# CW340_USERIO_Header.net
KiCad netlist of a schematic drawn in Altium Designer
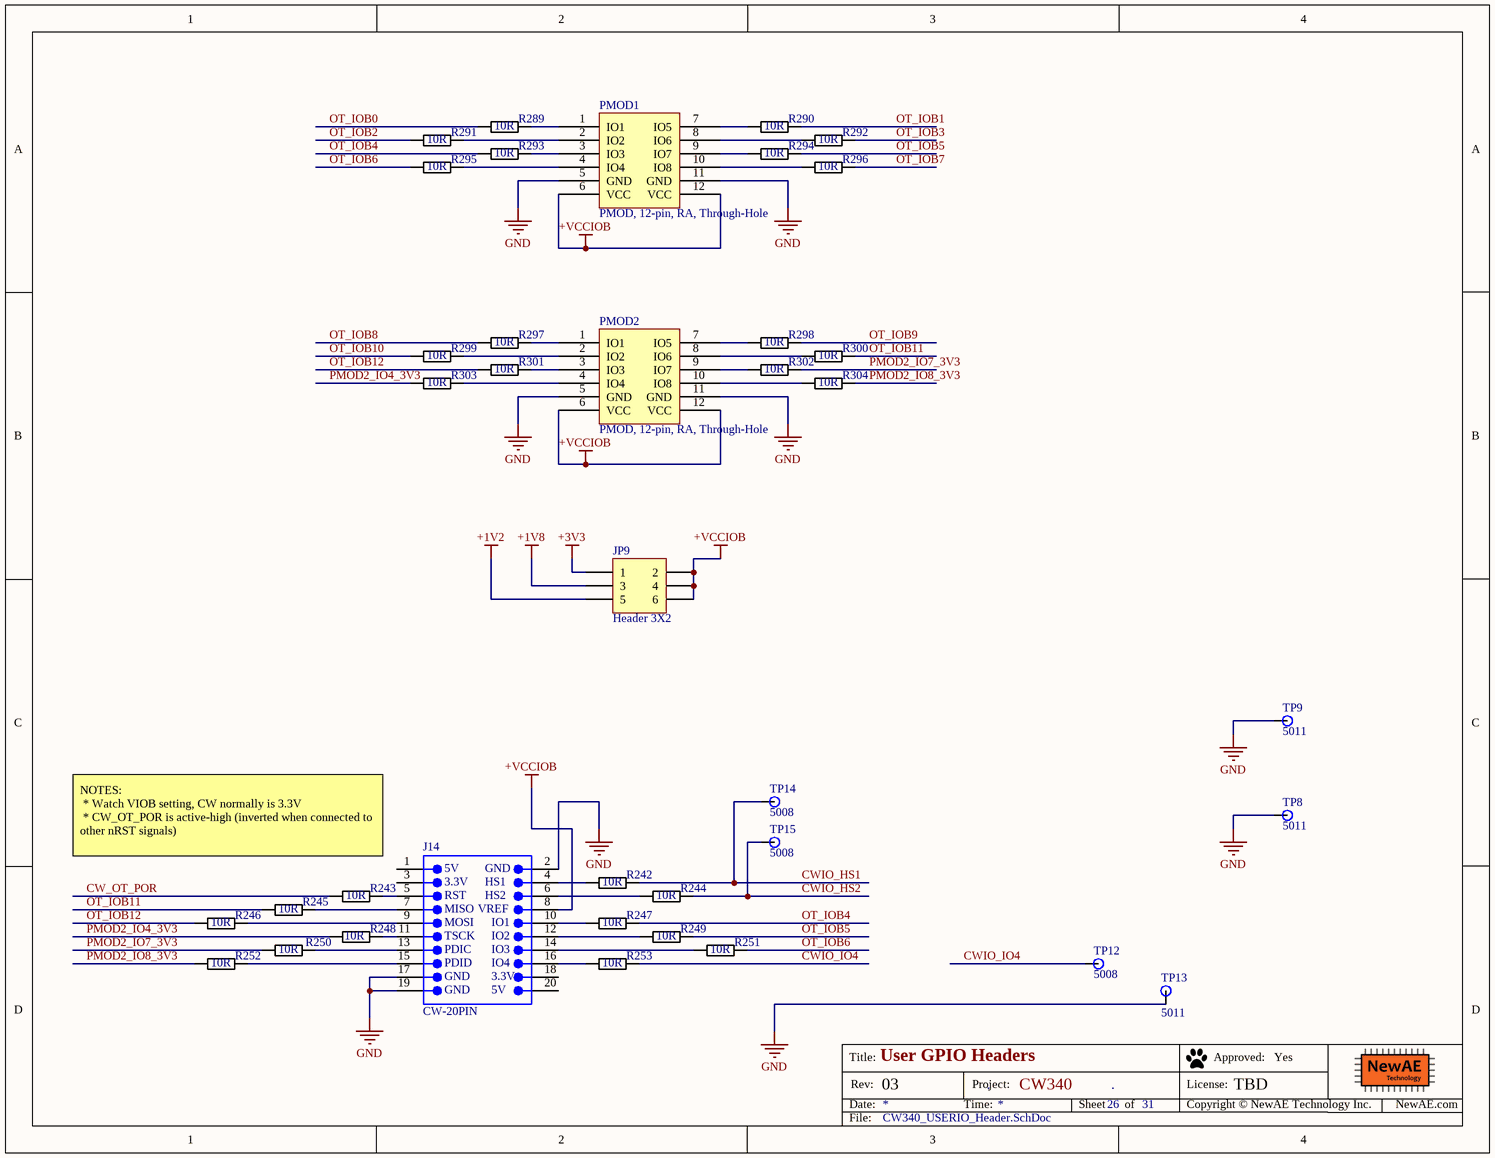
[diagram p0: CW340_USERIO_Header.SchDoc]

(export (version "E")
  (design (tool "Eeschema 10.0.6"))
  (components
    (comp (ref "J14")
      (value "CW-20PIN")
      (footprint "CONN_10x2_SHROUDED_2.54mm")
      (fields (field (name "PART NUMBER") "CW20PIN_TH"))
      (libsource (lib "NewAE_AltiumLib") (part "CW20PIN_TH_RA"))
    )
    (comp (ref "JP9")
      (value "Header 3X2")
      (footprint "HDR2X3")
      (description "Header, 3-Pin, Dual row")
      (fields (field (name "PUBLISHER") "Altium Limited"))
      (libsource (lib "Miscellaneous Connectors") (part "Header 3X2"))
    )
    (comp (ref "PMOD1")
      (value "PMOD, 12-pin, RA, Through-Hole")
      (footprint "SAMTEC_SSW_106_02_X_D_RA_PMOD")
      (fields (field (name "PART NUMBER") "PMOD_2ROW_FEMALERATH"))
      (libsource (lib "NewAE_AltiumLib") (part "12PIN_RA_FEMALE"))
    )
    (comp (ref "PMOD2")
      (value "PMOD, 12-pin, RA, Through-Hole")
      (footprint "SAMTEC_SSW_106_02_X_D_RA_PMOD")
      (fields (field (name "PART NUMBER") "PMOD_2ROW_FEMALERATH"))
      (libsource (lib "NewAE_AltiumLib") (part "12PIN_RA_FEMALE"))
    )
    (comp (ref "R242")
      (value "10R")
      (footprint "RESC1005X40N")
      (description "10R res, 0402, 1%, 1/16W")
      (fields (field (name "PART NUMBER") "RCHIP-10R-0402") (field (name "TOLERANCE") "1%"))
      (libsource (lib "NewAE_AltiumLib") (part "RES-EU"))
    )
    (comp (ref "R243")
      (value "10R")
      (footprint "RESC1005X40N")
      (description "10R res, 0402, 1%, 1/16W")
      (fields (field (name "PART NUMBER") "RCHIP-10R-0402") (field (name "TOLERANCE") "1%"))
      (libsource (lib "NewAE_AltiumLib") (part "RES-EU"))
    )
    (comp (ref "R244")
      (value "10R")
      (footprint "RESC1005X40N")
      (description "10R res, 0402, 1%, 1/16W")
      (fields (field (name "PART NUMBER") "RCHIP-10R-0402") (field (name "TOLERANCE") "1%"))
      (libsource (lib "NewAE_AltiumLib") (part "RES-EU"))
    )
    (comp (ref "R245")
      (value "10R")
      (footprint "RESC1005X40N")
      (description "10R res, 0402, 1%, 1/16W")
      (fields (field (name "PART NUMBER") "RCHIP-10R-0402") (field (name "TOLERANCE") "1%"))
      (libsource (lib "NewAE_AltiumLib") (part "RES-EU"))
    )
    (comp (ref "R246")
      (value "10R")
      (footprint "RESC1005X40N")
      (description "10R res, 0402, 1%, 1/16W")
      (fields (field (name "PART NUMBER") "RCHIP-10R-0402") (field (name "TOLERANCE") "1%"))
      (libsource (lib "NewAE_AltiumLib") (part "RES-EU"))
    )
    (comp (ref "R247")
      (value "10R")
      (footprint "RESC1005X40N")
      (description "10R res, 0402, 1%, 1/16W")
      (fields (field (name "PART NUMBER") "RCHIP-10R-0402") (field (name "TOLERANCE") "1%"))
      (libsource (lib "NewAE_AltiumLib") (part "RES-EU"))
    )
    (comp (ref "R248")
      (value "10R")
      (footprint "RESC1005X40N")
      (description "10R res, 0402, 1%, 1/16W")
      (fields (field (name "PART NUMBER") "RCHIP-10R-0402") (field (name "TOLERANCE") "1%"))
      (libsource (lib "NewAE_AltiumLib") (part "RES-EU"))
    )
    (comp (ref "R249")
      (value "10R")
      (footprint "RESC1005X40N")
      (description "10R res, 0402, 1%, 1/16W")
      (fields (field (name "PART NUMBER") "RCHIP-10R-0402") (field (name "TOLERANCE") "1%"))
      (libsource (lib "NewAE_AltiumLib") (part "RES-EU"))
    )
    (comp (ref "R250")
      (value "10R")
      (footprint "RESC1005X40N")
      (description "10R res, 0402, 1%, 1/16W")
      (fields (field (name "PART NUMBER") "RCHIP-10R-0402") (field (name "TOLERANCE") "1%"))
      (libsource (lib "NewAE_AltiumLib") (part "RES-EU"))
    )
    (comp (ref "R251")
      (value "10R")
      (footprint "RESC1005X40N")
      (description "10R res, 0402, 1%, 1/16W")
      (fields (field (name "PART NUMBER") "RCHIP-10R-0402") (field (name "TOLERANCE") "1%"))
      (libsource (lib "NewAE_AltiumLib") (part "RES-EU"))
    )
    (comp (ref "R252")
      (value "10R")
      (footprint "RESC1005X40N")
      (description "10R res, 0402, 1%, 1/16W")
      (fields (field (name "PART NUMBER") "RCHIP-10R-0402") (field (name "TOLERANCE") "1%"))
      (libsource (lib "NewAE_AltiumLib") (part "RES-EU"))
    )
    (comp (ref "R253")
      (value "10R")
      (footprint "RESC1005X40N")
      (description "10R res, 0402, 1%, 1/16W")
      (fields (field (name "PART NUMBER") "RCHIP-10R-0402") (field (name "TOLERANCE") "1%"))
      (libsource (lib "NewAE_AltiumLib") (part "RES-EU"))
    )
    (comp (ref "R289")
      (value "10R")
      (footprint "RESC1005X40N")
      (description "10R res, 0402, 1%, 1/16W")
      (fields (field (name "PART NUMBER") "RCHIP-10R-0402") (field (name "TOLERANCE") "1%"))
      (libsource (lib "NewAE_AltiumLib") (part "RES-EU"))
    )
    (comp (ref "R290")
      (value "10R")
      (footprint "RESC1005X40N")
      (description "10R res, 0402, 1%, 1/16W")
      (fields (field (name "PART NUMBER") "RCHIP-10R-0402") (field (name "TOLERANCE") "1%"))
      (libsource (lib "NewAE_AltiumLib") (part "RES-EU"))
    )
    (comp (ref "R291")
      (value "10R")
      (footprint "RESC1005X40N")
      (description "10R res, 0402, 1%, 1/16W")
      (fields (field (name "PART NUMBER") "RCHIP-10R-0402") (field (name "TOLERANCE") "1%"))
      (libsource (lib "NewAE_AltiumLib") (part "RES-EU"))
    )
    (comp (ref "R292")
      (value "10R")
      (footprint "RESC1005X40N")
      (description "10R res, 0402, 1%, 1/16W")
      (fields (field (name "PART NUMBER") "RCHIP-10R-0402") (field (name "TOLERANCE") "1%"))
      (libsource (lib "NewAE_AltiumLib") (part "RES-EU"))
    )
    (comp (ref "R293")
      (value "10R")
      (footprint "RESC1005X40N")
      (description "10R res, 0402, 1%, 1/16W")
      (fields (field (name "PART NUMBER") "RCHIP-10R-0402") (field (name "TOLERANCE") "1%"))
      (libsource (lib "NewAE_AltiumLib") (part "RES-EU"))
    )
    (comp (ref "R294")
      (value "10R")
      (footprint "RESC1005X40N")
      (description "10R res, 0402, 1%, 1/16W")
      (fields (field (name "PART NUMBER") "RCHIP-10R-0402") (field (name "TOLERANCE") "1%"))
      (libsource (lib "NewAE_AltiumLib") (part "RES-EU"))
    )
    (comp (ref "R295")
      (value "10R")
      (footprint "RESC1005X40N")
      (description "10R res, 0402, 1%, 1/16W")
      (fields (field (name "PART NUMBER") "RCHIP-10R-0402") (field (name "TOLERANCE") "1%"))
      (libsource (lib "NewAE_AltiumLib") (part "RES-EU"))
    )
    (comp (ref "R296")
      (value "10R")
      (footprint "RESC1005X40N")
      (description "10R res, 0402, 1%, 1/16W")
      (fields (field (name "PART NUMBER") "RCHIP-10R-0402") (field (name "TOLERANCE") "1%"))
      (libsource (lib "NewAE_AltiumLib") (part "RES-EU"))
    )
    (comp (ref "R297")
      (value "10R")
      (footprint "RESC1005X40N")
      (description "10R res, 0402, 1%, 1/16W")
      (fields (field (name "PART NUMBER") "RCHIP-10R-0402") (field (name "TOLERANCE") "1%"))
      (libsource (lib "NewAE_AltiumLib") (part "RES-EU"))
    )
    (comp (ref "R298")
      (value "10R")
      (footprint "RESC1005X40N")
      (description "10R res, 0402, 1%, 1/16W")
      (fields (field (name "PART NUMBER") "RCHIP-10R-0402") (field (name "TOLERANCE") "1%"))
      (libsource (lib "NewAE_AltiumLib") (part "RES-EU"))
    )
    (comp (ref "R299")
      (value "10R")
      (footprint "RESC1005X40N")
      (description "10R res, 0402, 1%, 1/16W")
      (fields (field (name "PART NUMBER") "RCHIP-10R-0402") (field (name "TOLERANCE") "1%"))
      (libsource (lib "NewAE_AltiumLib") (part "RES-EU"))
    )
    (comp (ref "R300")
      (value "10R")
      (footprint "RESC1005X40N")
      (description "10R res, 0402, 1%, 1/16W")
      (fields (field (name "PART NUMBER") "RCHIP-10R-0402") (field (name "TOLERANCE") "1%"))
      (libsource (lib "NewAE_AltiumLib") (part "RES-EU"))
    )
    (comp (ref "R301")
      (value "10R")
      (footprint "RESC1005X40N")
      (description "10R res, 0402, 1%, 1/16W")
      (fields (field (name "PART NUMBER") "RCHIP-10R-0402") (field (name "TOLERANCE") "1%"))
      (libsource (lib "NewAE_AltiumLib") (part "RES-EU"))
    )
    (comp (ref "R302")
      (value "10R")
      (footprint "RESC1005X40N")
      (description "10R res, 0402, 1%, 1/16W")
      (fields (field (name "PART NUMBER") "RCHIP-10R-0402") (field (name "TOLERANCE") "1%"))
      (libsource (lib "NewAE_AltiumLib") (part "RES-EU"))
    )
    (comp (ref "R303")
      (value "10R")
      (footprint "RESC1005X40N")
      (description "10R res, 0402, 1%, 1/16W")
      (fields (field (name "PART NUMBER") "RCHIP-10R-0402") (field (name "TOLERANCE") "1%"))
      (libsource (lib "NewAE_AltiumLib") (part "RES-EU"))
    )
    (comp (ref "R304")
      (value "10R")
      (footprint "RESC1005X40N")
      (description "10R res, 0402, 1%, 1/16W")
      (fields (field (name "PART NUMBER") "RCHIP-10R-0402") (field (name "TOLERANCE") "1%"))
      (libsource (lib "NewAE_AltiumLib") (part "RES-EU"))
    )
    (comp (ref "TP8")
      (value "5011")
      (footprint "KEYSTONE5011")
      (description "TEST POINT PC MULTI PURPOSE BLK")
      (fields (field (name "PART NUMBER") "KEYSTONE_5011"))
      (libsource (lib "NewAE_AltiumLib") (part "KEYSTONE_5011"))
    )
    (comp (ref "TP9")
      (value "5011")
      (footprint "KEYSTONE5011")
      (description "TEST POINT PC MULTI PURPOSE BLK")
      (fields (field (name "PART NUMBER") "KEYSTONE_5011"))
      (libsource (lib "NewAE_AltiumLib") (part "KEYSTONE_5011"))
    )
    (comp (ref "TP12")
      (value "5008")
      (footprint "KEYSTONE5008")
      (description "TEST POINT PC COMPACT .063\"D ORG")
      (fields (field (name "PART NUMBER") "KEYSTONE_5008"))
      (libsource (lib "NewAE_AltiumLib") (part "KEYSTONE_5008"))
    )
    (comp (ref "TP13")
      (value "5011")
      (footprint "KEYSTONE5011")
      (description "TEST POINT PC MULTI PURPOSE BLK")
      (fields (field (name "PART NUMBER") "KEYSTONE_5011"))
      (libsource (lib "NewAE_AltiumLib") (part "KEYSTONE_5011"))
    )
    (comp (ref "TP14")
      (value "5008")
      (footprint "KEYSTONE5008")
      (description "TEST POINT PC COMPACT .063\"D ORG")
      (fields (field (name "PART NUMBER") "KEYSTONE_5008"))
      (libsource (lib "NewAE_AltiumLib") (part "KEYSTONE_5008"))
    )
    (comp (ref "TP15")
      (value "5008")
      (footprint "KEYSTONE5008")
      (description "TEST POINT PC COMPACT .063\"D ORG")
      (fields (field (name "PART NUMBER") "KEYSTONE_5008"))
      (libsource (lib "NewAE_AltiumLib") (part "KEYSTONE_5008"))
    )
  )
  (nets
    (net (code "1") (name "+1V2") (class "Default")
      (node (ref "JP9") (pin "5") (pinfunction "5_5") (pintype "passive"))
    )
    (net (code "2") (name "+1V8") (class "Default")
      (node (ref "JP9") (pin "3") (pinfunction "3_3") (pintype "passive"))
    )
    (net (code "3") (name "+3V3") (class "Default")
      (node (ref "JP9") (pin "1") (pinfunction "1_1") (pintype "passive"))
    )
    (net (code "4") (name "+VCCIOB") (class "Default")
      (node (ref "J14") (pin "8") (pinfunction "8_8") (pintype "passive"))
      (node (ref "JP9") (pin "2") (pinfunction "2_2") (pintype "passive"))
      (node (ref "JP9") (pin "4") (pinfunction "4_4") (pintype "passive"))
      (node (ref "JP9") (pin "6") (pinfunction "6_6") (pintype "passive"))
      (node (ref "PMOD1") (pin "12") (pinfunction "VCC_12") (pintype "passive"))
      (node (ref "PMOD1") (pin "6") (pinfunction "VCC_6") (pintype "passive"))
      (node (ref "PMOD2") (pin "12") (pinfunction "VCC_12") (pintype "passive"))
      (node (ref "PMOD2") (pin "6") (pinfunction "VCC_6") (pintype "passive"))
    )
    (net (code "5") (name "/CWIO_HS1") (class "Default")
      (node (ref "R242") (pin "2") (pinfunction "2_2") (pintype "passive"))
      (node (ref "TP14") (pin "1") (pinfunction "1_1") (pintype "passive"))
    )
    (net (code "6") (name "/CWIO_HS2") (class "Default")
      (node (ref "R244") (pin "2") (pinfunction "2_2") (pintype "passive"))
      (node (ref "TP15") (pin "1") (pinfunction "1_1") (pintype "passive"))
    )
    (net (code "7") (name "/CWIO_IO4") (class "Default")
      (node (ref "R253") (pin "2") (pinfunction "2_2") (pintype "passive"))
      (node (ref "TP12") (pin "1") (pinfunction "1_1") (pintype "passive"))
    )
    (net (code "8") (name "/CW_OT_POR") (class "Default")
      (node (ref "R243") (pin "1") (pinfunction "1_1") (pintype "passive"))
    )
    (net (code "9") (name "/OT_IOB0") (class "Default")
      (node (ref "R289") (pin "1") (pinfunction "1_1") (pintype "passive"))
    )
    (net (code "10") (name "/OT_IOB1") (class "Default")
      (node (ref "R290") (pin "2") (pinfunction "2_2") (pintype "passive"))
    )
    (net (code "11") (name "/OT_IOB2") (class "Default")
      (node (ref "R291") (pin "1") (pinfunction "1_1") (pintype "passive"))
    )
    (net (code "12") (name "/OT_IOB3") (class "Default")
      (node (ref "R292") (pin "2") (pinfunction "2_2") (pintype "passive"))
    )
    (net (code "13") (name "/OT_IOB4") (class "Default")
      (node (ref "R247") (pin "2") (pinfunction "2_2") (pintype "passive"))
      (node (ref "R293") (pin "1") (pinfunction "1_1") (pintype "passive"))
    )
    (net (code "14") (name "/OT_IOB5") (class "Default")
      (node (ref "R249") (pin "2") (pinfunction "2_2") (pintype "passive"))
      (node (ref "R294") (pin "2") (pinfunction "2_2") (pintype "passive"))
    )
    (net (code "15") (name "/OT_IOB6") (class "Default")
      (node (ref "R251") (pin "2") (pinfunction "2_2") (pintype "passive"))
      (node (ref "R295") (pin "1") (pinfunction "1_1") (pintype "passive"))
    )
    (net (code "16") (name "/OT_IOB7") (class "Default")
      (node (ref "R296") (pin "2") (pinfunction "2_2") (pintype "passive"))
    )
    (net (code "17") (name "/OT_IOB8") (class "Default")
      (node (ref "R297") (pin "1") (pinfunction "1_1") (pintype "passive"))
    )
    (net (code "18") (name "/OT_IOB9") (class "Default")
      (node (ref "R298") (pin "2") (pinfunction "2_2") (pintype "passive"))
    )
    (net (code "19") (name "/OT_IOB10") (class "Default")
      (node (ref "R299") (pin "1") (pinfunction "1_1") (pintype "passive"))
    )
    (net (code "20") (name "/OT_IOB11") (class "Default")
      (node (ref "R245") (pin "1") (pinfunction "1_1") (pintype "passive"))
      (node (ref "R300") (pin "2") (pinfunction "2_2") (pintype "passive"))
    )
    (net (code "21") (name "/OT_IOB12") (class "Default")
      (node (ref "R246") (pin "1") (pinfunction "1_1") (pintype "passive"))
      (node (ref "R301") (pin "1") (pinfunction "1_1") (pintype "passive"))
    )
    (net (code "22") (name "/PMOD2_IO4_3V3") (class "Default")
      (node (ref "R248") (pin "1") (pinfunction "1_1") (pintype "passive"))
      (node (ref "R303") (pin "1") (pinfunction "1_1") (pintype "passive"))
    )
    (net (code "23") (name "/PMOD2_IO7_3V3") (class "Default")
      (node (ref "R250") (pin "1") (pinfunction "1_1") (pintype "passive"))
      (node (ref "R302") (pin "2") (pinfunction "2_2") (pintype "passive"))
    )
    (net (code "24") (name "/PMOD2_IO8_3V3") (class "Default")
      (node (ref "R252") (pin "1") (pinfunction "1_1") (pintype "passive"))
      (node (ref "R304") (pin "2") (pinfunction "2_2") (pintype "passive"))
    )
    (net (code "25") (name "GND") (class "Default")
      (node (ref "J14") (pin "17") (pinfunction "17_17") (pintype "passive"))
      (node (ref "J14") (pin "19") (pinfunction "19_19") (pintype "passive"))
      (node (ref "J14") (pin "2") (pinfunction "2_2") (pintype "passive"))
      (node (ref "PMOD1") (pin "11") (pinfunction "GND_11") (pintype "passive"))
      (node (ref "PMOD1") (pin "5") (pinfunction "GND_5") (pintype "passive"))
      (node (ref "PMOD2") (pin "11") (pinfunction "GND_11") (pintype "passive"))
      (node (ref "PMOD2") (pin "5") (pinfunction "GND_5") (pintype "passive"))
      (node (ref "TP13") (pin "1") (pinfunction "1_1") (pintype "passive"))
      (node (ref "TP8") (pin "1") (pinfunction "1_1") (pintype "passive"))
      (node (ref "TP9") (pin "1") (pinfunction "1_1") (pintype "passive"))
    )
    (net (code "26") (name "Net-(J14-Pad4)") (class "Default")
      (node (ref "J14") (pin "4") (pinfunction "4_4") (pintype "passive"))
      (node (ref "R242") (pin "1") (pinfunction "1_1") (pintype "passive"))
    )
    (net (code "27") (name "Net-(J14-Pad5)") (class "Default")
      (node (ref "J14") (pin "5") (pinfunction "5_5") (pintype "passive"))
      (node (ref "R243") (pin "2") (pinfunction "2_2") (pintype "passive"))
    )
    (net (code "28") (name "Net-(J14-Pad6)") (class "Default")
      (node (ref "J14") (pin "6") (pinfunction "6_6") (pintype "passive"))
      (node (ref "R244") (pin "1") (pinfunction "1_1") (pintype "passive"))
    )
    (net (code "29") (name "Net-(J14-Pad7)") (class "Default")
      (node (ref "J14") (pin "7") (pinfunction "7_7") (pintype "passive"))
      (node (ref "R245") (pin "2") (pinfunction "2_2") (pintype "passive"))
    )
    (net (code "30") (name "Net-(J14-Pad9)") (class "Default")
      (node (ref "J14") (pin "9") (pinfunction "9_9") (pintype "passive"))
      (node (ref "R246") (pin "2") (pinfunction "2_2") (pintype "passive"))
    )
    (net (code "31") (name "Net-(J14-Pad10)") (class "Default")
      (node (ref "J14") (pin "10") (pinfunction "10_10") (pintype "passive"))
      (node (ref "R247") (pin "1") (pinfunction "1_1") (pintype "passive"))
    )
    (net (code "32") (name "Net-(J14-Pad11)") (class "Default")
      (node (ref "J14") (pin "11") (pinfunction "11_11") (pintype "passive"))
      (node (ref "R248") (pin "2") (pinfunction "2_2") (pintype "passive"))
    )
    (net (code "33") (name "Net-(J14-Pad12)") (class "Default")
      (node (ref "J14") (pin "12") (pinfunction "12_12") (pintype "passive"))
      (node (ref "R249") (pin "1") (pinfunction "1_1") (pintype "passive"))
    )
    (net (code "34") (name "Net-(J14-Pad13)") (class "Default")
      (node (ref "J14") (pin "13") (pinfunction "13_13") (pintype "passive"))
      (node (ref "R250") (pin "2") (pinfunction "2_2") (pintype "passive"))
    )
    (net (code "35") (name "Net-(J14-Pad14)") (class "Default")
      (node (ref "J14") (pin "14") (pinfunction "14_14") (pintype "passive"))
      (node (ref "R251") (pin "1") (pinfunction "1_1") (pintype "passive"))
    )
    (net (code "36") (name "Net-(J14-Pad15)") (class "Default")
      (node (ref "J14") (pin "15") (pinfunction "15_15") (pintype "passive"))
      (node (ref "R252") (pin "2") (pinfunction "2_2") (pintype "passive"))
    )
    (net (code "37") (name "Net-(J14-Pad16)") (class "Default")
      (node (ref "J14") (pin "16") (pinfunction "16_16") (pintype "passive"))
      (node (ref "R253") (pin "1") (pinfunction "1_1") (pintype "passive"))
    )
    (net (code "38") (name "Net-(PMOD1-IO1)") (class "Default")
      (node (ref "PMOD1") (pin "1") (pinfunction "IO1_1") (pintype "passive"))
      (node (ref "R289") (pin "2") (pinfunction "2_2") (pintype "passive"))
    )
    (net (code "39") (name "Net-(PMOD1-IO2)") (class "Default")
      (node (ref "PMOD1") (pin "2") (pinfunction "IO2_2") (pintype "passive"))
      (node (ref "R291") (pin "2") (pinfunction "2_2") (pintype "passive"))
    )
    (net (code "40") (name "Net-(PMOD1-IO3)") (class "Default")
      (node (ref "PMOD1") (pin "3") (pinfunction "IO3_3") (pintype "passive"))
      (node (ref "R293") (pin "2") (pinfunction "2_2") (pintype "passive"))
    )
    (net (code "41") (name "Net-(PMOD1-IO4)") (class "Default")
      (node (ref "PMOD1") (pin "4") (pinfunction "IO4_4") (pintype "passive"))
      (node (ref "R295") (pin "2") (pinfunction "2_2") (pintype "passive"))
    )
    (net (code "42") (name "Net-(PMOD1-IO5)") (class "Default")
      (node (ref "PMOD1") (pin "7") (pinfunction "IO5_7") (pintype "passive"))
      (node (ref "R290") (pin "1") (pinfunction "1_1") (pintype "passive"))
    )
    (net (code "43") (name "Net-(PMOD1-IO6)") (class "Default")
      (node (ref "PMOD1") (pin "8") (pinfunction "IO6_8") (pintype "passive"))
      (node (ref "R292") (pin "1") (pinfunction "1_1") (pintype "passive"))
    )
    (net (code "44") (name "Net-(PMOD1-IO7)") (class "Default")
      (node (ref "PMOD1") (pin "9") (pinfunction "IO7_9") (pintype "passive"))
      (node (ref "R294") (pin "1") (pinfunction "1_1") (pintype "passive"))
    )
    (net (code "45") (name "Net-(PMOD1-IO8)") (class "Default")
      (node (ref "PMOD1") (pin "10") (pinfunction "IO8_10") (pintype "passive"))
      (node (ref "R296") (pin "1") (pinfunction "1_1") (pintype "passive"))
    )
    (net (code "46") (name "Net-(PMOD2-IO1)") (class "Default")
      (node (ref "PMOD2") (pin "1") (pinfunction "IO1_1") (pintype "passive"))
      (node (ref "R297") (pin "2") (pinfunction "2_2") (pintype "passive"))
    )
    (net (code "47") (name "Net-(PMOD2-IO2)") (class "Default")
      (node (ref "PMOD2") (pin "2") (pinfunction "IO2_2") (pintype "passive"))
      (node (ref "R299") (pin "2") (pinfunction "2_2") (pintype "passive"))
    )
    (net (code "48") (name "Net-(PMOD2-IO3)") (class "Default")
      (node (ref "PMOD2") (pin "3") (pinfunction "IO3_3") (pintype "passive"))
      (node (ref "R301") (pin "2") (pinfunction "2_2") (pintype "passive"))
    )
    (net (code "49") (name "Net-(PMOD2-IO4)") (class "Default")
      (node (ref "PMOD2") (pin "4") (pinfunction "IO4_4") (pintype "passive"))
      (node (ref "R303") (pin "2") (pinfunction "2_2") (pintype "passive"))
    )
    (net (code "50") (name "Net-(PMOD2-IO5)") (class "Default")
      (node (ref "PMOD2") (pin "7") (pinfunction "IO5_7") (pintype "passive"))
      (node (ref "R298") (pin "1") (pinfunction "1_1") (pintype "passive"))
    )
    (net (code "51") (name "Net-(PMOD2-IO6)") (class "Default")
      (node (ref "PMOD2") (pin "8") (pinfunction "IO6_8") (pintype "passive"))
      (node (ref "R300") (pin "1") (pinfunction "1_1") (pintype "passive"))
    )
    (net (code "52") (name "Net-(PMOD2-IO7)") (class "Default")
      (node (ref "PMOD2") (pin "9") (pinfunction "IO7_9") (pintype "passive"))
      (node (ref "R302") (pin "1") (pinfunction "1_1") (pintype "passive"))
    )
    (net (code "53") (name "Net-(PMOD2-IO8)") (class "Default")
      (node (ref "PMOD2") (pin "10") (pinfunction "IO8_10") (pintype "passive"))
      (node (ref "R304") (pin "1") (pinfunction "1_1") (pintype "passive"))
    )
    (net (code "54") (name "unconnected-(J14-Pad1)") (class "Default")
      (node (ref "J14") (pin "1") (pinfunction "1_1") (pintype "passive"))
    )
    (net (code "55") (name "unconnected-(J14-Pad3)") (class "Default")
      (node (ref "J14") (pin "3") (pinfunction "3_3") (pintype "passive"))
    )
    (net (code "56") (name "unconnected-(J14-Pad18)") (class "Default")
      (node (ref "J14") (pin "18") (pinfunction "18_18") (pintype "passive"))
    )
    (net (code "57") (name "unconnected-(J14-Pad20)") (class "Default")
      (node (ref "J14") (pin "20") (pinfunction "20_20") (pintype "passive"))
    )
  )
)
